# Divider.net
KiCad netlist of a schematic drawn in Altium Designer
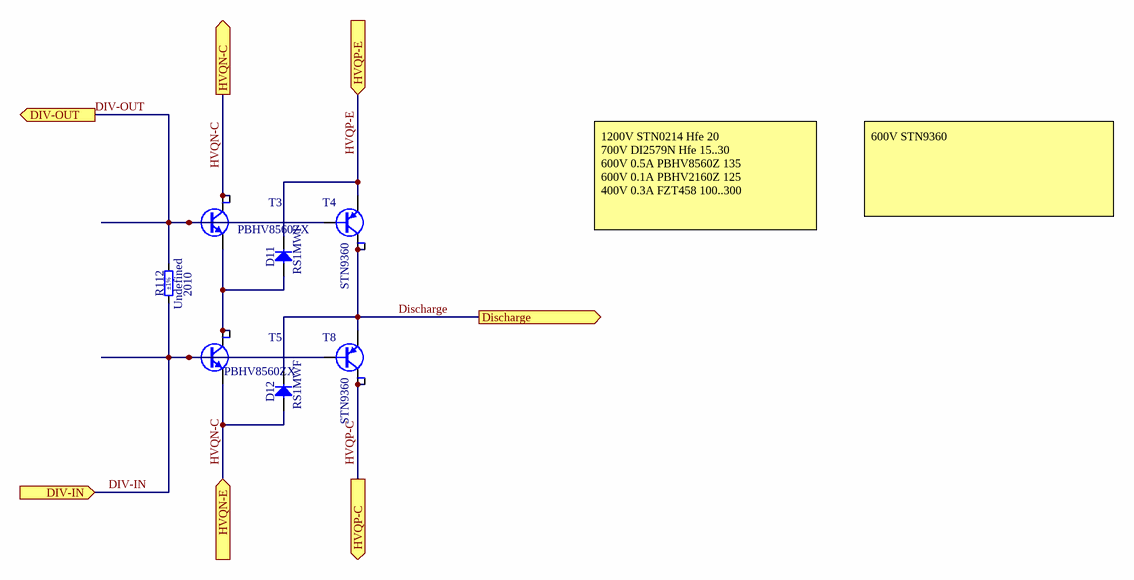
[diagram p0: Divider.SchDoc]

(export (version "E")
  (design (tool "Eeschema 10.0.6"))
  (components
    (comp (ref "D11")
      (value "RS1MWF")
      (footprint "SOD-123F")
      (description "Diode")
      (fields
        (field (name "VOLTAGE") "1000V")
        (field (name "POWER") "1A")
        (field (name "AUTHOR") "CERN DEM HF")
      )
      (libsource (lib "ICs And Semiconductors") (part "Diode"))
    )
    (comp (ref "D12")
      (value "RS1MWF")
      (footprint "SOD-123F")
      (description "Diode")
      (fields
        (field (name "VOLTAGE") "1000V")
        (field (name "POWER") "1A")
        (field (name "AUTHOR") "CERN DEM HF")
      )
      (libsource (lib "ICs And Semiconductors") (part "Diode"))
    )
    (comp (ref "R112")
      (value "Undefined")
      (footprint "RES_VISHAY_CRHV2010A")
      (description "Resistor - 1%")
      (fields
        (field (name "TOLERANCE") "±1%")
        (field (name "POWER") "0.5W")
        (field (name "MANUFACTURER") "VISHAY TECHNO")
        (field (name "CASE") "2010")
        (field (name "AUTHOR") "CERN DEM JLC")
      )
      (libsource (lib "Resistors") (part "Resistor - 1%"))
    )
    (comp (ref "T3")
      (value "PBHV8560ZX")
      (footprint "SOT230P700X180-4N")
      (description "600 V, 0.5 A NPN high-voltage low VCEsat (BISS) transistor")
      (fields (field (name "MANUFACTURER") "Nexperia") (field (name "AUTHOR") "GK"))
      (libsource (lib "Tranistors_Thyristors") (part "Q_PBHV8560Z"))
    )
    (comp (ref "T4")
      (value "STN9360")
      (footprint "SOT230P700X180-4N")
      (description "PNP Transistor")
      (fields (field (name "MANUFACTURER") "STMicroelectronics") (field (name "AUTHOR") "FS"))
      (libsource (lib "templib") (part "STN9360"))
    )
    (comp (ref "T5")
      (value "PBHV8560ZX")
      (footprint "SOT230P700X180-4N")
      (description "600 V, 0.5 A NPN high-voltage low VCEsat (BISS) transistor")
      (fields (field (name "MANUFACTURER") "Nexperia") (field (name "AUTHOR") "GK"))
      (libsource (lib "Tranistors_Thyristors") (part "Q_PBHV8560Z"))
    )
    (comp (ref "T8")
      (value "STN9360")
      (footprint "SOT230P700X180-4N")
      (description "PNP Transistor")
      (fields (field (name "MANUFACTURER") "STMicroelectronics") (field (name "AUTHOR") "FS"))
      (libsource (lib "templib") (part "STN9360"))
    )
  )
  (nets
    (net (code "1") (name "/DIV-IN") (class "Default")
      (node (ref "R112") (pin "1") (pinfunction "1_1") (pintype "passive"))
      (node (ref "T5") (pin "1") (pinfunction "B_1") (pintype "passive"))
      (node (ref "T8") (pin "1") (pinfunction "B_1") (pintype "passive"))
    )
    (net (code "2") (name "/DIV-OUT") (class "Default")
      (node (ref "R112") (pin "2") (pinfunction "2_2") (pintype "passive"))
      (node (ref "T3") (pin "1") (pinfunction "B_1") (pintype "passive"))
      (node (ref "T4") (pin "1") (pinfunction "B_1") (pintype "passive"))
    )
    (net (code "3") (name "/Discharge") (class "Default")
      (node (ref "D12") (pin "1") (pinfunction "C_1") (pintype "passive"))
      (node (ref "T4") (pin "2") (pinfunction "C_2") (pintype "passive"))
      (node (ref "T4") (pin "4") (pinfunction "C_4") (pintype "passive"))
      (node (ref "T8") (pin "3") (pinfunction "E_3") (pintype "passive"))
    )
    (net (code "4") (name "/HVQN-C") (class "Default")
      (node (ref "D12") (pin "2") (pinfunction "A_2") (pintype "passive"))
      (node (ref "T3") (pin "2") (pinfunction "C_2") (pintype "passive"))
      (node (ref "T3") (pin "4") (pinfunction "C_4") (pintype "passive"))
      (node (ref "T5") (pin "3") (pinfunction "E_3") (pintype "passive"))
    )
    (net (code "5") (name "/HVQP-C") (class "Default")
      (node (ref "T8") (pin "2") (pinfunction "C_2") (pintype "passive"))
      (node (ref "T8") (pin "4") (pinfunction "C_4") (pintype "passive"))
    )
    (net (code "6") (name "/HVQP-E") (class "Default")
      (node (ref "D11") (pin "1") (pinfunction "C_1") (pintype "passive"))
      (node (ref "T4") (pin "3") (pinfunction "E_3") (pintype "passive"))
    )
    (net (code "7") (name "Net-(D11-A)") (class "Default")
      (node (ref "D11") (pin "2") (pinfunction "A_2") (pintype "passive"))
      (node (ref "T3") (pin "3") (pinfunction "E_3") (pintype "passive"))
      (node (ref "T5") (pin "2") (pinfunction "C_2") (pintype "passive"))
      (node (ref "T5") (pin "4") (pinfunction "C_4") (pintype "passive"))
    )
  )
)
